# TeensyLED_15042100.net
KiCad netlist of a schematic drawn in EAGLE
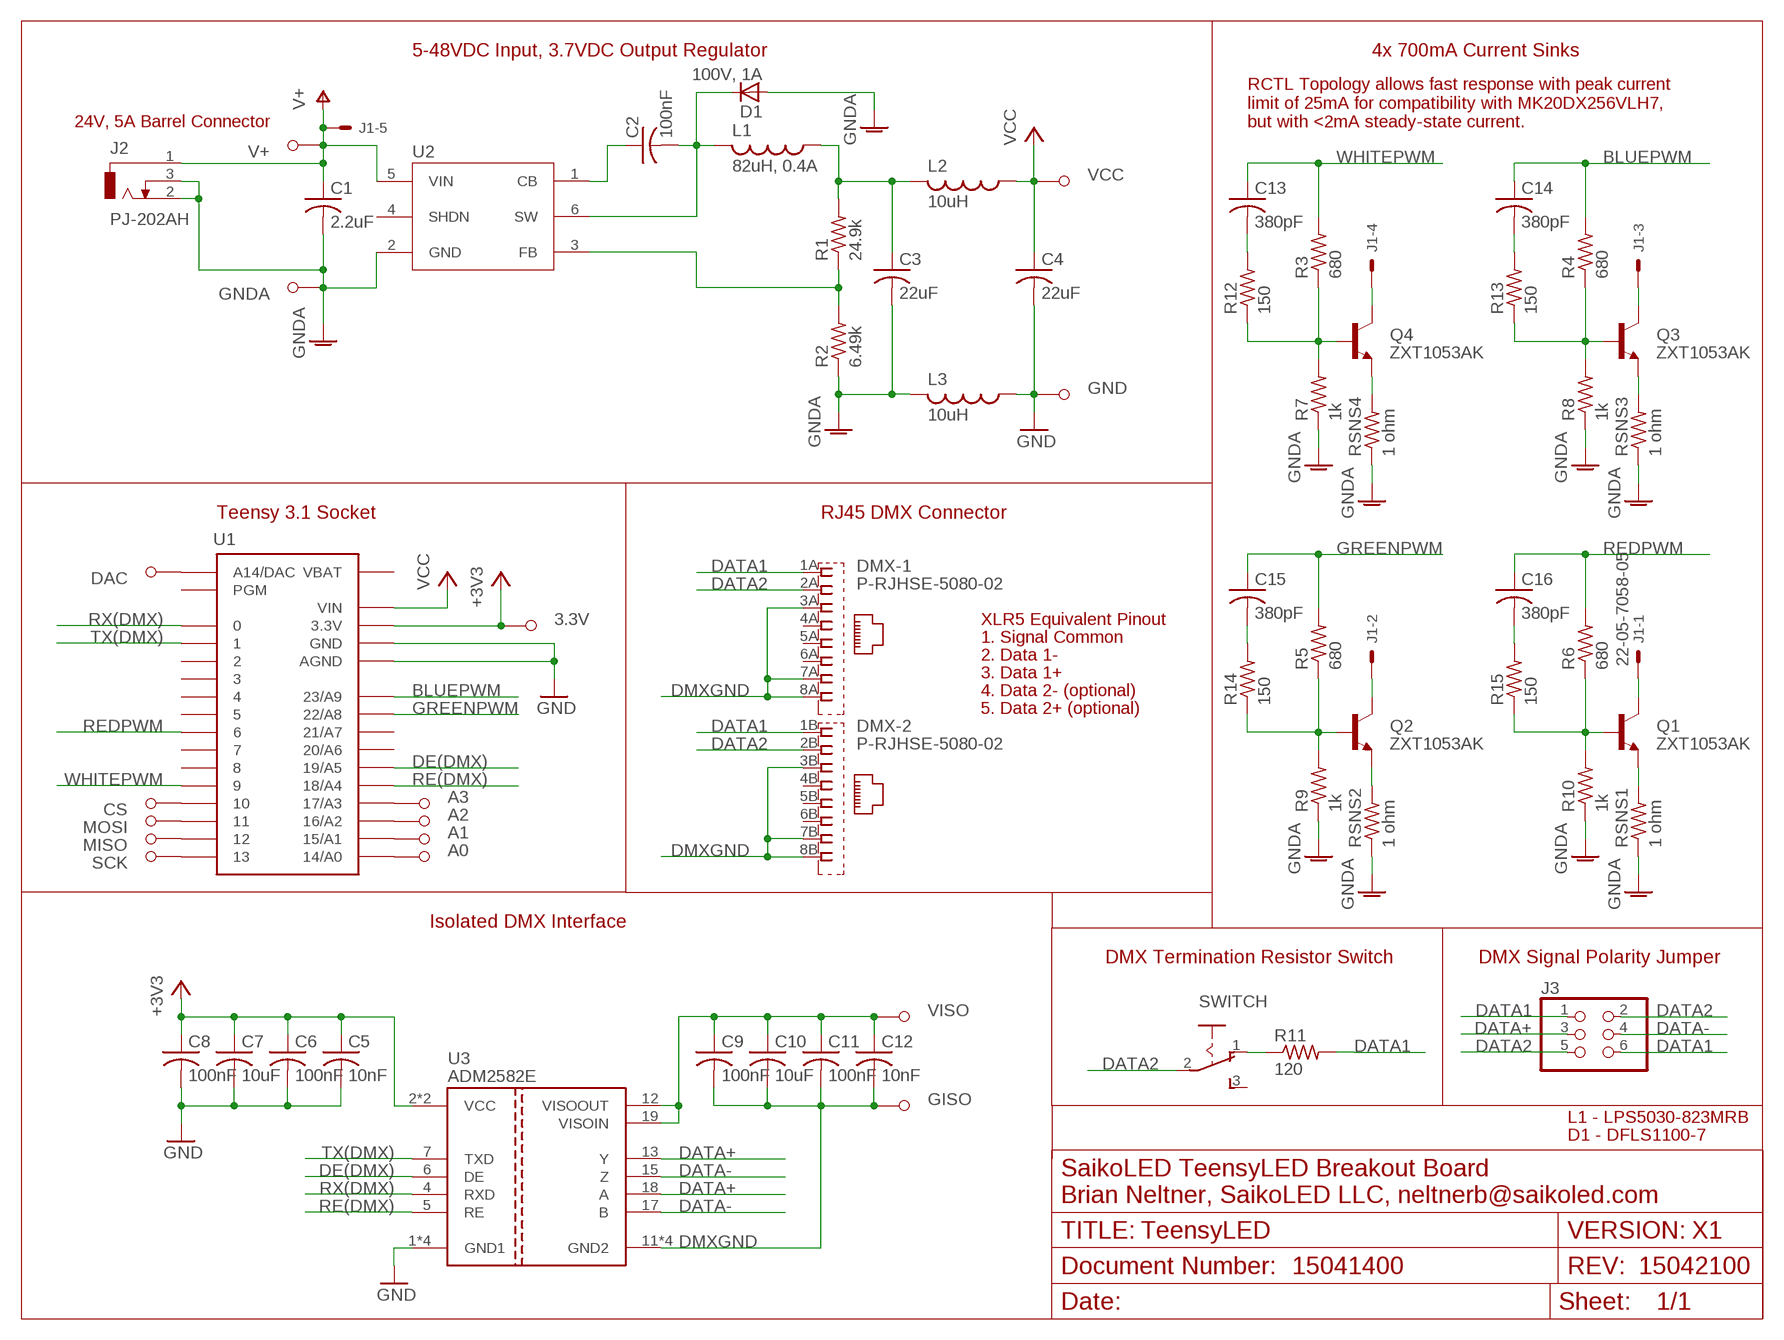
[diagram p0: schematic, sheet 1]

(export (version "E")
  (design (tool "Eeschema 10.0.6"))
  (components
    (comp (ref "3.3V")
      (value "TESTPOINT5019")
      (footprint "eagle-import:5019")
      (libsource (lib "eagle-import") (part "TESTPOINT5019"))
    )
    (comp (ref "A0")
      (value "TESTPOINT5019")
      (footprint "eagle-import:5019")
      (libsource (lib "eagle-import") (part "TESTPOINT5019"))
    )
    (comp (ref "A1")
      (value "TESTPOINT5019")
      (footprint "eagle-import:5019")
      (libsource (lib "eagle-import") (part "TESTPOINT5019"))
    )
    (comp (ref "A2")
      (value "TESTPOINT5019")
      (footprint "eagle-import:5019")
      (libsource (lib "eagle-import") (part "TESTPOINT5019"))
    )
    (comp (ref "A3")
      (value "TESTPOINT5019")
      (footprint "eagle-import:5019")
      (libsource (lib "eagle-import") (part "TESTPOINT5019"))
    )
    (comp (ref "C1")
      (value "2.2uF")
      (footprint "eagle-import:C1210K")
      (libsource (lib "eagle-import") (part "C-USC1210K"))
    )
    (comp (ref "C2")
      (value "100nF")
      (footprint "eagle-import:C0805K")
      (libsource (lib "eagle-import") (part "C-USC0805K"))
    )
    (comp (ref "C3")
      (value "22uF")
      (footprint "eagle-import:C0805K")
      (fields (field (name "MF") "Multicomp Passives") (field (name "MPN") "MCLV4R7M1HB-0513-RH"))
      (libsource (lib "eagle-import") (part "C-USC0805K"))
    )
    (comp (ref "C4")
      (value "22uF")
      (footprint "eagle-import:C0805K")
      (libsource (lib "eagle-import") (part "C-USC0805K"))
    )
    (comp (ref "C5")
      (value "10nF")
      (footprint "eagle-import:C0402PRO")
      (libsource (lib "eagle-import") (part "C-USC0402PRO"))
    )
    (comp (ref "C6")
      (value "100nF")
      (footprint "eagle-import:C0402PRO")
      (libsource (lib "eagle-import") (part "C-USC0402PRO"))
    )
    (comp (ref "C7")
      (value "10uF")
      (footprint "eagle-import:C0402PRO")
      (libsource (lib "eagle-import") (part "C-USC0402PRO"))
    )
    (comp (ref "C8")
      (value "100nF")
      (footprint "eagle-import:C0402PRO")
      (libsource (lib "eagle-import") (part "C-USC0402PRO"))
    )
    (comp (ref "C9")
      (value "100nF")
      (footprint "eagle-import:C0402PRO")
      (libsource (lib "eagle-import") (part "C-USC0402PRO"))
    )
    (comp (ref "C10")
      (value "10uF")
      (footprint "eagle-import:C0402PRO")
      (libsource (lib "eagle-import") (part "C-USC0402PRO"))
    )
    (comp (ref "C11")
      (value "100nF")
      (footprint "eagle-import:C0402PRO")
      (libsource (lib "eagle-import") (part "C-USC0402PRO"))
    )
    (comp (ref "C12")
      (value "10nF")
      (footprint "eagle-import:C0402PRO")
      (libsource (lib "eagle-import") (part "C-USC0402PRO"))
    )
    (comp (ref "C13")
      (value "380pF")
      (footprint "eagle-import:C0402PRO")
      (libsource (lib "eagle-import") (part "C-USC0402PRO"))
    )
    (comp (ref "C14")
      (value "380pF")
      (footprint "eagle-import:C0402PRO")
      (libsource (lib "eagle-import") (part "C-USC0402PRO"))
    )
    (comp (ref "C15")
      (value "380pF")
      (footprint "eagle-import:C0402PRO")
      (libsource (lib "eagle-import") (part "C-USC0402PRO"))
    )
    (comp (ref "C16")
      (value "380pF")
      (footprint "eagle-import:C0402PRO")
      (libsource (lib "eagle-import") (part "C-USC0402PRO"))
    )
    (comp (ref "CS")
      (value "TESTPOINT5019")
      (footprint "eagle-import:5019")
      (libsource (lib "eagle-import") (part "TESTPOINT5019"))
    )
    (comp (ref "D1")
      (value "100V, 1A")
      (footprint "eagle-import:DFLS1100")
      (libsource (lib "eagle-import") (part "DFLS1100"))
    )
    (comp (ref "DAC")
      (value "TESTPOINT5019")
      (footprint "eagle-import:5019")
      (libsource (lib "eagle-import") (part "TESTPOINT5019"))
    )
    (comp (ref "DMX")
      (value "P-RJHSE-5080-02")
      (footprint "eagle-import:P-RJHSE-5080-02")
      (libsource (lib "eagle-import") (part "P-RJHSE-5080-02"))
    )
    (comp (ref "FRAME1")
      (value "LETTER_L")
      (footprint "eagle-import:PCBINFO")
      (libsource (lib "eagle-import") (part "LETTER_L"))
    )
    (comp (ref "GISO")
      (value "TESTPOINT5019")
      (footprint "eagle-import:5019")
      (libsource (lib "eagle-import") (part "TESTPOINT5019"))
    )
    (comp (ref "GND")
      (value "TESTPOINT5019")
      (footprint "eagle-import:5019")
      (libsource (lib "eagle-import") (part "TESTPOINT5019"))
    )
    (comp (ref "GNDA")
      (value "TESTPOINT5019")
      (footprint "eagle-import:5019")
      (libsource (lib "eagle-import") (part "TESTPOINT5019"))
    )
    (comp (ref "J1")
      (value "22-05-7058-05")
      (footprint "eagle-import:7395-05")
      (libsource (lib "eagle-import") (part "22-?-0505-7058"))
    )
    (comp (ref "J2")
      (value "PJ-202AH")
      (footprint "eagle-import:PJ-202AH")
      (libsource (lib "eagle-import") (part "PJ-202AH"))
    )
    (comp (ref "J3")
      (value "PINHD-2X3")
      (footprint "eagle-import:2X03")
      (libsource (lib "eagle-import") (part "PINHD-2X3"))
    )
    (comp (ref "L1")
      (value "82uH, 0.4A")
      (footprint "eagle-import:LPS5030")
      (libsource (lib "eagle-import") (part "L-US"))
    )
    (comp (ref "L2")
      (value "10uH")
      (footprint "eagle-import:L2012C")
      (libsource (lib "eagle-import") (part "rcl_L-USL2012C"))
    )
    (comp (ref "L3")
      (value "10uH")
      (footprint "eagle-import:L2012C")
      (libsource (lib "eagle-import") (part "rcl_L-USL2012C"))
    )
    (comp (ref "MISO")
      (value "TESTPOINT5019")
      (footprint "eagle-import:5019")
      (libsource (lib "eagle-import") (part "TESTPOINT5019"))
    )
    (comp (ref "MOSI")
      (value "TESTPOINT5019")
      (footprint "eagle-import:5019")
      (libsource (lib "eagle-import") (part "TESTPOINT5019"))
    )
    (comp (ref "Q1")
      (value "ZXT1053AK")
      (footprint "eagle-import:TO252")
      (libsource (lib "eagle-import") (part "ZXT1053AK"))
    )
    (comp (ref "Q2")
      (value "ZXT1053AK")
      (footprint "eagle-import:TO252")
      (libsource (lib "eagle-import") (part "ZXT1053AK"))
    )
    (comp (ref "Q3")
      (value "ZXT1053AK")
      (footprint "eagle-import:TO252")
      (libsource (lib "eagle-import") (part "ZXT1053AK"))
    )
    (comp (ref "Q4")
      (value "ZXT1053AK")
      (footprint "eagle-import:TO252")
      (libsource (lib "eagle-import") (part "ZXT1053AK"))
    )
    (comp (ref "R1")
      (value "24.9k")
      (footprint "eagle-import:R0402PRO")
      (fields (field (name "MPN") "BLU0402-9762-BT25W"))
      (libsource (lib "eagle-import") (part "R-US_R0402PRO"))
    )
    (comp (ref "R2")
      (value "6.49k")
      (footprint "eagle-import:R0402PRO")
      (fields (field (name "MPN") "ERJ-3EKF4123V"))
      (libsource (lib "eagle-import") (part "R-US_R0402PRO"))
    )
    (comp (ref "R3")
      (value "680")
      (footprint "eagle-import:R0402PRO")
      (libsource (lib "eagle-import") (part "R-US_R0402PRO"))
    )
    (comp (ref "R4")
      (value "680")
      (footprint "eagle-import:R0402PRO")
      (libsource (lib "eagle-import") (part "R-US_R0402PRO"))
    )
    (comp (ref "R5")
      (value "680")
      (footprint "eagle-import:R0402PRO")
      (libsource (lib "eagle-import") (part "R-US_R0402PRO"))
    )
    (comp (ref "R6")
      (value "680")
      (footprint "eagle-import:R0402PRO")
      (libsource (lib "eagle-import") (part "R-US_R0402PRO"))
    )
    (comp (ref "R7")
      (value "1k")
      (footprint "eagle-import:R0402PRO")
      (libsource (lib "eagle-import") (part "R-US_R0402PRO"))
    )
    (comp (ref "R8")
      (value "1k")
      (footprint "eagle-import:R0402PRO")
      (libsource (lib "eagle-import") (part "R-US_R0402PRO"))
    )
    (comp (ref "R9")
      (value "1k")
      (footprint "eagle-import:R0402PRO")
      (libsource (lib "eagle-import") (part "R-US_R0402PRO"))
    )
    (comp (ref "R10")
      (value "1k")
      (footprint "eagle-import:R0402PRO")
      (libsource (lib "eagle-import") (part "R-US_R0402PRO"))
    )
    (comp (ref "R11")
      (value "120")
      (footprint "eagle-import:R0402PRO")
      (libsource (lib "eagle-import") (part "R-US_R0402PRO"))
    )
    (comp (ref "R12")
      (value "150")
      (footprint "eagle-import:R0402PRO")
      (libsource (lib "eagle-import") (part "R-US_R0402PRO"))
    )
    (comp (ref "R13")
      (value "150")
      (footprint "eagle-import:R0402PRO")
      (libsource (lib "eagle-import") (part "R-US_R0402PRO"))
    )
    (comp (ref "R14")
      (value "150")
      (footprint "eagle-import:R0402PRO")
      (libsource (lib "eagle-import") (part "R-US_R0402PRO"))
    )
    (comp (ref "R15")
      (value "150")
      (footprint "eagle-import:R0402PRO")
      (libsource (lib "eagle-import") (part "R-US_R0402PRO"))
    )
    (comp (ref "RSNS1")
      (value "1 ohm")
      (footprint "eagle-import:R1206")
      (libsource (lib "eagle-import") (part "R-US_R1206"))
    )
    (comp (ref "RSNS2")
      (value "1 ohm")
      (footprint "eagle-import:R1206")
      (libsource (lib "eagle-import") (part "R-US_R1206"))
    )
    (comp (ref "RSNS3")
      (value "1 ohm")
      (footprint "eagle-import:R1206")
      (libsource (lib "eagle-import") (part "R-US_R1206"))
    )
    (comp (ref "RSNS4")
      (value "1 ohm")
      (footprint "eagle-import:R1206")
      (libsource (lib "eagle-import") (part "R-US_R1206"))
    )
    (comp (ref "SCK")
      (value "TESTPOINT5019")
      (footprint "eagle-import:5019")
      (libsource (lib "eagle-import") (part "TESTPOINT5019"))
    )
    (comp (ref "SWITCH")
      (value "M251")
      (footprint "eagle-import:SK-12F17-G")
      (libsource (lib "eagle-import") (part "M251"))
    )
    (comp (ref "U1")
      (value "TEENSY_3.0_BASIC")
      (footprint "eagle-import:TEENSY_3.0_BASIC")
      (libsource (lib "eagle-import") (part "TEENSY_3.0_BASIC"))
    )
    (comp (ref "U2")
      (value "LMR16006YDDCT")
      (footprint "eagle-import:DDC0006A")
      (fields
        (field (name "MANUFACTURER") "Texas Instruments")
        (field (name "PARTNUMBER") "LMR16006YDDC")
        (field (name "MF") "FARNELL")
      )
      (libsource (lib "eagle-import") (part "LMR16006YDDCT"))
    )
    (comp (ref "U3")
      (value "ADM2582E")
      (footprint "eagle-import:SO-20DW")
      (libsource (lib "eagle-import") (part "ADM2582E"))
    )
    (comp (ref "V+")
      (value "TESTPOINT5019")
      (footprint "eagle-import:5019")
      (libsource (lib "eagle-import") (part "TESTPOINT5019"))
    )
    (comp (ref "VCC")
      (value "TESTPOINT5019")
      (footprint "eagle-import:5019")
      (libsource (lib "eagle-import") (part "TESTPOINT5019"))
    )
    (comp (ref "VISO")
      (value "TESTPOINT5019")
      (footprint "eagle-import:5019")
      (libsource (lib "eagle-import") (part "TESTPOINT5019"))
    )
  )
  (nets
    (net (code "1") (name "+3V3") (class "Default")
      (node (ref "3.3V") (pin "P$1") (pinfunction "P$1_P$1") (pintype "passive"))
      (node (ref "C5") (pin "1") (pinfunction "1_1") (pintype "passive"))
      (node (ref "C6") (pin "1") (pinfunction "1_1") (pintype "passive"))
      (node (ref "C7") (pin "1") (pinfunction "1_1") (pintype "passive"))
      (node (ref "C8") (pin "1") (pinfunction "1_1") (pintype "passive"))
      (node (ref "U1") (pin "3.3V") (pinfunction "3.3V_3.3V") (pintype "power_in"))
      (node (ref "U1") (pin "3.3V1") (pinfunction "3.3V_3.3V1") (pintype "power_in"))
      (node (ref "U3") (pin "2") (pinfunction "VCC_2") (pintype "bidirectional"))
      (node (ref "U3") (pin "8") (pinfunction "VCC_8") (pintype "bidirectional"))
    )
    (net (code "2") (name "/BLUEPWM") (class "Default")
      (node (ref "C14") (pin "1") (pinfunction "1_1") (pintype "passive"))
      (node (ref "R4") (pin "2") (pinfunction "2_2") (pintype "passive"))
      (node (ref "U1") (pin "23/A9") (pinfunction "23/A9_23/A9") (pintype "bidirectional"))
    )
    (net (code "3") (name "/DATA+") (class "Default")
      (node (ref "J3") (pin "3") (pinfunction "3_3") (pintype "passive"))
      (node (ref "U3") (pin "13") (pinfunction "Y_13") (pintype "bidirectional"))
      (node (ref "U3") (pin "18") (pinfunction "A_18") (pintype "bidirectional"))
    )
    (net (code "4") (name "/DATA-") (class "Default")
      (node (ref "J3") (pin "4") (pinfunction "4_4") (pintype "passive"))
      (node (ref "U3") (pin "15") (pinfunction "Z_15") (pintype "bidirectional"))
      (node (ref "U3") (pin "17") (pinfunction "B_17") (pintype "bidirectional"))
    )
    (net (code "5") (name "/DATA1") (class "Default")
      (node (ref "DMX") (pin "1A") (pinfunction "1_1A") (pintype "passive"))
      (node (ref "DMX") (pin "1B") (pinfunction "1_1B") (pintype "passive"))
      (node (ref "J3") (pin "1") (pinfunction "1_1") (pintype "passive"))
      (node (ref "J3") (pin "6") (pinfunction "6_6") (pintype "passive"))
      (node (ref "R11") (pin "2") (pinfunction "2_2") (pintype "passive"))
    )
    (net (code "6") (name "/DATA2") (class "Default")
      (node (ref "DMX") (pin "2A") (pinfunction "2_2A") (pintype "passive"))
      (node (ref "DMX") (pin "2B") (pinfunction "2_2B") (pintype "passive"))
      (node (ref "J3") (pin "2") (pinfunction "2_2") (pintype "passive"))
      (node (ref "J3") (pin "5") (pinfunction "5_5") (pintype "passive"))
      (node (ref "SWITCH") (pin "2") (pinfunction "P_2") (pintype "passive"))
    )
    (net (code "7") (name "/DE(DMX)") (class "Default")
      (node (ref "U1") (pin "19/A5") (pinfunction "19/A5_19/A5") (pintype "bidirectional"))
      (node (ref "U3") (pin "6") (pinfunction "DE_6") (pintype "bidirectional"))
    )
    (net (code "8") (name "/DMXGND") (class "Default")
      (node (ref "C10") (pin "2") (pinfunction "2_2") (pintype "passive"))
      (node (ref "C11") (pin "2") (pinfunction "2_2") (pintype "passive"))
      (node (ref "C12") (pin "2") (pinfunction "2_2") (pintype "passive"))
      (node (ref "C9") (pin "2") (pinfunction "2_2") (pintype "passive"))
      (node (ref "DMX") (pin "3A") (pinfunction "3_3A") (pintype "passive"))
      (node (ref "DMX") (pin "3B") (pinfunction "3_3B") (pintype "passive"))
      (node (ref "DMX") (pin "7A") (pinfunction "7_7A") (pintype "passive"))
      (node (ref "DMX") (pin "7B") (pinfunction "7_7B") (pintype "passive"))
      (node (ref "DMX") (pin "8A") (pinfunction "8_8A") (pintype "passive"))
      (node (ref "DMX") (pin "8B") (pinfunction "8_8B") (pintype "passive"))
      (node (ref "GISO") (pin "P$1") (pinfunction "P$1_P$1") (pintype "passive"))
      (node (ref "U3") (pin "11") (pinfunction "GND2_11") (pintype "bidirectional"))
      (node (ref "U3") (pin "14") (pinfunction "GND2_14") (pintype "bidirectional"))
      (node (ref "U3") (pin "16") (pinfunction "GND2_16") (pintype "bidirectional"))
      (node (ref "U3") (pin "20") (pinfunction "GND2_20") (pintype "bidirectional"))
    )
    (net (code "9") (name "/GREENPWM") (class "Default")
      (node (ref "C15") (pin "1") (pinfunction "1_1") (pintype "passive"))
      (node (ref "R5") (pin "2") (pinfunction "2_2") (pintype "passive"))
      (node (ref "U1") (pin "22/A8") (pinfunction "22/A8_22/A8") (pintype "bidirectional"))
    )
    (net (code "10") (name "/RE(DMX)") (class "Default")
      (node (ref "U1") (pin "18/A4") (pinfunction "18/A4_18/A4") (pintype "bidirectional"))
      (node (ref "U3") (pin "5") (pinfunction "RE_5") (pintype "bidirectional"))
    )
    (net (code "11") (name "/REDPWM") (class "Default")
      (node (ref "C16") (pin "1") (pinfunction "1_1") (pintype "passive"))
      (node (ref "R6") (pin "2") (pinfunction "2_2") (pintype "passive"))
      (node (ref "U1") (pin "6") (pinfunction "6_6") (pintype "bidirectional"))
    )
    (net (code "12") (name "/RX(DMX)") (class "Default")
      (node (ref "U1") (pin "0") (pinfunction "0_0") (pintype "bidirectional"))
      (node (ref "U3") (pin "4") (pinfunction "RXD_4") (pintype "bidirectional"))
    )
    (net (code "13") (name "/TX(DMX)") (class "Default")
      (node (ref "U1") (pin "1") (pinfunction "1_1") (pintype "bidirectional"))
      (node (ref "U3") (pin "7") (pinfunction "TXD_7") (pintype "bidirectional"))
    )
    (net (code "14") (name "/VBAT") (class "Default")
      (node (ref "U1") (pin "VBAT") (pinfunction "VBAT_VBAT") (pintype "power_in"))
    )
    (net (code "15") (name "/WHITEPWM") (class "Default")
      (node (ref "C13") (pin "1") (pinfunction "1_1") (pintype "passive"))
      (node (ref "R3") (pin "2") (pinfunction "2_2") (pintype "passive"))
      (node (ref "U1") (pin "9") (pinfunction "9_9") (pintype "bidirectional"))
    )
    (net (code "16") (name "GND") (class "Default")
      (node (ref "C4") (pin "2") (pinfunction "2_2") (pintype "passive"))
      (node (ref "C5") (pin "2") (pinfunction "2_2") (pintype "passive"))
      (node (ref "C6") (pin "2") (pinfunction "2_2") (pintype "passive"))
      (node (ref "C7") (pin "2") (pinfunction "2_2") (pintype "passive"))
      (node (ref "C8") (pin "2") (pinfunction "2_2") (pintype "passive"))
      (node (ref "GND") (pin "P$1") (pinfunction "P$1_P$1") (pintype "passive"))
      (node (ref "L3") (pin "1") (pinfunction "1_1") (pintype "passive"))
      (node (ref "U1") (pin "AGND") (pinfunction "AGND_AGND") (pintype "power_in"))
      (node (ref "U1") (pin "GND") (pinfunction "GND_GND") (pintype "power_in"))
      (node (ref "U1") (pin "GND1") (pinfunction "GND_GND1") (pintype "power_in"))
      (node (ref "U3") (pin "1") (pinfunction "GND1_1") (pintype "bidirectional"))
      (node (ref "U3") (pin "10") (pinfunction "GND1_10") (pintype "bidirectional"))
      (node (ref "U3") (pin "3") (pinfunction "GND1_3") (pintype "bidirectional"))
      (node (ref "U3") (pin "9") (pinfunction "GND1_9") (pintype "bidirectional"))
    )
    (net (code "17") (name "GNDA") (class "Default")
      (node (ref "C1") (pin "2") (pinfunction "2_2") (pintype "passive"))
      (node (ref "C3") (pin "2") (pinfunction "2_2") (pintype "passive"))
      (node (ref "D1") (pin "A") (pinfunction "A_A") (pintype "passive"))
      (node (ref "GNDA") (pin "P$1") (pinfunction "P$1_P$1") (pintype "passive"))
      (node (ref "J2") (pin "2") (pinfunction "3_2") (pintype "passive"))
      (node (ref "J2") (pin "3") (pinfunction "2_3") (pintype "passive"))
      (node (ref "L3") (pin "2") (pinfunction "2_2") (pintype "passive"))
      (node (ref "R10") (pin "1") (pinfunction "1_1") (pintype "passive"))
      (node (ref "R2") (pin "1") (pinfunction "1_1") (pintype "passive"))
      (node (ref "R7") (pin "1") (pinfunction "1_1") (pintype "passive"))
      (node (ref "R8") (pin "1") (pinfunction "1_1") (pintype "passive"))
      (node (ref "R9") (pin "1") (pinfunction "1_1") (pintype "passive"))
      (node (ref "RSNS1") (pin "1") (pinfunction "1_1") (pintype "passive"))
      (node (ref "RSNS2") (pin "1") (pinfunction "1_1") (pintype "passive"))
      (node (ref "RSNS3") (pin "1") (pinfunction "1_1") (pintype "passive"))
      (node (ref "RSNS4") (pin "1") (pinfunction "1_1") (pintype "passive"))
      (node (ref "U2") (pin "2") (pinfunction "GND_2") (pintype "power_in"))
    )
    (net (code "18") (name "Net-(A0-PadP$1)") (class "Default")
      (node (ref "A0") (pin "P$1") (pinfunction "P$1_P$1") (pintype "passive"))
      (node (ref "U1") (pin "14/A0") (pinfunction "14/A0_14/A0") (pintype "bidirectional"))
    )
    (net (code "19") (name "Net-(A1-PadP$1)") (class "Default")
      (node (ref "A1") (pin "P$1") (pinfunction "P$1_P$1") (pintype "passive"))
      (node (ref "U1") (pin "15/A1") (pinfunction "15/A1_15/A1") (pintype "bidirectional"))
    )
    (net (code "20") (name "Net-(A2-PadP$1)") (class "Default")
      (node (ref "A2") (pin "P$1") (pinfunction "P$1_P$1") (pintype "passive"))
      (node (ref "U1") (pin "16/A2") (pinfunction "16/A2_16/A2") (pintype "bidirectional"))
    )
    (net (code "21") (name "Net-(A3-PadP$1)") (class "Default")
      (node (ref "A3") (pin "P$1") (pinfunction "P$1_P$1") (pintype "passive"))
      (node (ref "U1") (pin "17/A3") (pinfunction "17/A3_17/A3") (pintype "bidirectional"))
    )
    (net (code "22") (name "Net-(C13-Pad2)") (class "Default")
      (node (ref "C13") (pin "2") (pinfunction "2_2") (pintype "passive"))
      (node (ref "R12") (pin "2") (pinfunction "2_2") (pintype "passive"))
    )
    (net (code "23") (name "Net-(C14-Pad2)") (class "Default")
      (node (ref "C14") (pin "2") (pinfunction "2_2") (pintype "passive"))
      (node (ref "R13") (pin "2") (pinfunction "2_2") (pintype "passive"))
    )
    (net (code "24") (name "Net-(C15-Pad2)") (class "Default")
      (node (ref "C15") (pin "2") (pinfunction "2_2") (pintype "passive"))
      (node (ref "R14") (pin "2") (pinfunction "2_2") (pintype "passive"))
    )
    (net (code "25") (name "Net-(C16-Pad2)") (class "Default")
      (node (ref "C16") (pin "2") (pinfunction "2_2") (pintype "passive"))
      (node (ref "R15") (pin "2") (pinfunction "2_2") (pintype "passive"))
    )
    (net (code "26") (name "Net-(CS-PadP$1)") (class "Default")
      (node (ref "CS") (pin "P$1") (pinfunction "P$1_P$1") (pintype "passive"))
      (node (ref "U1") (pin "10") (pinfunction "10_10") (pintype "bidirectional"))
    )
    (net (code "27") (name "Net-(J1A-S)") (class "Default")
      (node (ref "J1") (pin "1") (pinfunction "S_1") (pintype "passive"))
      (node (ref "Q1") (pin "C") (pinfunction "C_C") (pintype "passive"))
    )
    (net (code "28") (name "Net-(J1B-S)") (class "Default")
      (node (ref "J1") (pin "2") (pinfunction "S_2") (pintype "passive"))
      (node (ref "Q2") (pin "C") (pinfunction "C_C") (pintype "passive"))
    )
    (net (code "29") (name "Net-(J1C-S)") (class "Default")
      (node (ref "J1") (pin "3") (pinfunction "S_3") (pintype "passive"))
      (node (ref "Q3") (pin "C") (pinfunction "C_C") (pintype "passive"))
    )
    (net (code "30") (name "Net-(J1D-S)") (class "Default")
      (node (ref "J1") (pin "4") (pinfunction "S_4") (pintype "passive"))
      (node (ref "Q4") (pin "C") (pinfunction "C_C") (pintype "passive"))
    )
    (net (code "31") (name "Net-(L1-1)") (class "Default")
      (node (ref "C3") (pin "1") (pinfunction "1_1") (pintype "passive"))
      (node (ref "L1") (pin "P$1") (pinfunction "1_P$1") (pintype "passive"))
      (node (ref "L2") (pin "2") (pinfunction "2_2") (pintype "passive"))
      (node (ref "R1") (pin "2") (pinfunction "2_2") (pintype "passive"))
    )
    (net (code "32") (name "Net-(L1-2)") (class "Default")
      (node (ref "C2") (pin "2") (pinfunction "2_2") (pintype "passive"))
      (node (ref "D1") (pin "C") (pinfunction "C_C") (pintype "passive"))
      (node (ref "L1") (pin "P$2") (pinfunction "2_P$2") (pintype "passive"))
      (node (ref "U2") (pin "6") (pinfunction "SW_6") (pintype "power_in"))
    )
    (net (code "33") (name "Net-(MISO-PadP$1)") (class "Default")
      (node (ref "MISO") (pin "P$1") (pinfunction "P$1_P$1") (pintype "passive"))
      (node (ref "U1") (pin "12") (pinfunction "12_12") (pintype "bidirectional"))
    )
    (net (code "34") (name "Net-(MOSI-PadP$1)") (class "Default")
      (node (ref "MOSI") (pin "P$1") (pinfunction "P$1_P$1") (pintype "passive"))
      (node (ref "U1") (pin "11") (pinfunction "11_11") (pintype "bidirectional"))
    )
    (net (code "35") (name "Net-(Q1-PadB)") (class "Default")
      (node (ref "Q1") (pin "B") (pinfunction "B_B") (pintype "passive"))
      (node (ref "R10") (pin "2") (pinfunction "2_2") (pintype "passive"))
      (node (ref "R15") (pin "1") (pinfunction "1_1") (pintype "passive"))
      (node (ref "R6") (pin "1") (pinfunction "1_1") (pintype "passive"))
    )
    (net (code "36") (name "Net-(Q1-PadE)") (class "Default")
      (node (ref "Q1") (pin "E") (pinfunction "E_E") (pintype "passive"))
      (node (ref "RSNS1") (pin "2") (pinfunction "2_2") (pintype "passive"))
    )
    (net (code "37") (name "Net-(Q2-PadB)") (class "Default")
      (node (ref "Q2") (pin "B") (pinfunction "B_B") (pintype "passive"))
      (node (ref "R14") (pin "1") (pinfunction "1_1") (pintype "passive"))
      (node (ref "R5") (pin "1") (pinfunction "1_1") (pintype "passive"))
      (node (ref "R9") (pin "2") (pinfunction "2_2") (pintype "passive"))
    )
    (net (code "38") (name "Net-(Q2-PadE)") (class "Default")
      (node (ref "Q2") (pin "E") (pinfunction "E_E") (pintype "passive"))
      (node (ref "RSNS2") (pin "2") (pinfunction "2_2") (pintype "passive"))
    )
    (net (code "39") (name "Net-(Q3-PadB)") (class "Default")
      (node (ref "Q3") (pin "B") (pinfunction "B_B") (pintype "passive"))
      (node (ref "R13") (pin "1") (pinfunction "1_1") (pintype "passive"))
      (node (ref "R4") (pin "1") (pinfunction "1_1") (pintype "passive"))
      (node (ref "R8") (pin "2") (pinfunction "2_2") (pintype "passive"))
    )
    (net (code "40") (name "Net-(Q3-PadE)") (class "Default")
      (node (ref "Q3") (pin "E") (pinfunction "E_E") (pintype "passive"))
      (node (ref "RSNS3") (pin "2") (pinfunction "2_2") (pintype "passive"))
    )
    (net (code "41") (name "Net-(Q4-PadB)") (class "Default")
      (node (ref "Q4") (pin "B") (pinfunction "B_B") (pintype "passive"))
      (node (ref "R12") (pin "1") (pinfunction "1_1") (pintype "passive"))
      (node (ref "R3") (pin "1") (pinfunction "1_1") (pintype "passive"))
      (node (ref "R7") (pin "2") (pinfunction "2_2") (pintype "passive"))
    )
    (net (code "42") (name "Net-(Q4-PadE)") (class "Default")
      (node (ref "Q4") (pin "E") (pinfunction "E_E") (pintype "passive"))
      (node (ref "RSNS4") (pin "2") (pinfunction "2_2") (pintype "passive"))
    )
    (net (code "43") (name "Net-(SCK-PadP$1)") (class "Default")
      (node (ref "SCK") (pin "P$1") (pinfunction "P$1_P$1") (pintype "passive"))
      (node (ref "U1") (pin "13") (pinfunction "13_13") (pintype "bidirectional"))
    )
    (net (code "44") (name "Net-(SWITCH-O)") (class "Default")
      (node (ref "R11") (pin "1") (pinfunction "1_1") (pintype "passive"))
      (node (ref "SWITCH") (pin "1") (pinfunction "O_1") (pintype "passive"))
    )
    (net (code "45") (name "Net-(U1-A14{slash}DAC)") (class "Default")
      (node (ref "DAC") (pin "P$1") (pinfunction "P$1_P$1") (pintype "passive"))
      (node (ref "U1") (pin "RESET") (pinfunction "A14/DAC_RESET") (pintype "bidirectional"))
    )
    (net (code "46") (name "Net-(U2-CB)") (class "Default")
      (node (ref "C2") (pin "1") (pinfunction "1_1") (pintype "passive"))
      (node (ref "U2") (pin "1") (pinfunction "CB_1") (pintype "output"))
    )
    (net (code "47") (name "Net-(U2-FB)") (class "Default")
      (node (ref "R1") (pin "1") (pinfunction "1_1") (pintype "passive"))
      (node (ref "R2") (pin "2") (pinfunction "2_2") (pintype "passive"))
      (node (ref "U2") (pin "3") (pinfunction "FB_3") (pintype "input"))
    )
    (net (code "48") (name "Net-(U3-VISOIN)") (class "Default")
      (node (ref "C10") (pin "1") (pinfunction "1_1") (pintype "passive"))
      (node (ref "C11") (pin "1") (pinfunction "1_1") (pintype "passive"))
      (node (ref "C12") (pin "1") (pinfunction "1_1") (pintype "passive"))
      (node (ref "C9") (pin "1") (pinfunction "1_1") (pintype "passive"))
      (node (ref "U3") (pin "12") (pinfunction "VISOOUT_12") (pintype "bidirectional"))
      (node (ref "U3") (pin "19") (pinfunction "VISOIN_19") (pintype "bidirectional"))
      (node (ref "VISO") (pin "P$1") (pinfunction "P$1_P$1") (pintype "passive"))
    )
    (net (code "49") (name "V+") (class "Default")
      (node (ref "C1") (pin "1") (pinfunction "1_1") (pintype "passive"))
      (node (ref "J1") (pin "5") (pinfunction "S_5") (pintype "passive"))
      (node (ref "J2") (pin "1") (pinfunction "1_1") (pintype "passive"))
      (node (ref "U2") (pin "5") (pinfunction "VIN_5") (pintype "power_in"))
      (node (ref "V+") (pin "P$1") (pinfunction "P$1_P$1") (pintype "passive"))
    )
    (net (code "50") (name "VCC") (class "Default")
      (node (ref "C4") (pin "1") (pinfunction "1_1") (pintype "passive"))
      (node (ref "L2") (pin "1") (pinfunction "1_1") (pintype "passive"))
      (node (ref "U1") (pin "VIN") (pinfunction "VIN_VIN") (pintype "power_in"))
      (node (ref "VCC") (pin "P$1") (pinfunction "P$1_P$1") (pintype "passive"))
    )
    (net (code "51") (name "unconnected-(DMXA-4-Pad4A)") (class "Default")
      (node (ref "DMX") (pin "4A") (pinfunction "4_4A") (pintype "passive"))
    )
    (net (code "52") (name "unconnected-(DMXA-5-Pad5A)") (class "Default")
      (node (ref "DMX") (pin "5A") (pinfunction "5_5A") (pintype "passive"))
    )
    (net (code "53") (name "unconnected-(DMXA-6-Pad6A)") (class "Default")
      (node (ref "DMX") (pin "6A") (pinfunction "6_6A") (pintype "passive"))
    )
    (net (code "54") (name "unconnected-(DMXB-4-Pad4B)") (class "Default")
      (node (ref "DMX") (pin "4B") (pinfunction "4_4B") (pintype "passive"))
    )
    (net (code "55") (name "unconnected-(DMXB-5-Pad5B)") (class "Default")
      (node (ref "DMX") (pin "5B") (pinfunction "5_5B") (pintype "passive"))
    )
    (net (code "56") (name "unconnected-(DMXB-6-Pad6B)") (class "Default")
      (node (ref "DMX") (pin "6B") (pinfunction "6_6B") (pintype "passive"))
    )
    (net (code "57") (name "unconnected-(SWITCH-S-Pad3)") (class "Default")
      (node (ref "SWITCH") (pin "3") (pinfunction "S_3") (pintype "passive"))
    )
    (net (code "58") (name "unconnected-(U1-Pad2)") (class "Default")
      (node (ref "U1") (pin "2") (pinfunction "2_2") (pintype "bidirectional"))
    )
    (net (code "59") (name "unconnected-(U1-Pad3)") (class "Default")
      (node (ref "U1") (pin "3") (pinfunction "3_3") (pintype "bidirectional"))
    )
    (net (code "60") (name "unconnected-(U1-Pad4)") (class "Default")
      (node (ref "U1") (pin "4") (pinfunction "4_4") (pintype "bidirectional"))
    )
    (net (code "61") (name "unconnected-(U1-Pad5)") (class "Default")
      (node (ref "U1") (pin "5") (pinfunction "5_5") (pintype "bidirectional"))
    )
    (net (code "62") (name "unconnected-(U1-Pad7)") (class "Default")
      (node (ref "U1") (pin "7") (pinfunction "7_7") (pintype "bidirectional"))
    )
    (net (code "63") (name "unconnected-(U1-Pad8)") (class "Default")
      (node (ref "U1") (pin "8") (pinfunction "8_8") (pintype "bidirectional"))
    )
    (net (code "64") (name "unconnected-(U1-Pad20{slash}A6)") (class "Default")
      (node (ref "U1") (pin "20/A6") (pinfunction "20/A6_20/A6") (pintype "bidirectional"))
    )
    (net (code "65") (name "unconnected-(U1-Pad21{slash}A7)") (class "Default")
      (node (ref "U1") (pin "21/A7") (pinfunction "21/A7_21/A7") (pintype "bidirectional"))
    )
    (net (code "66") (name "unconnected-(U1-PadPGM)") (class "Default")
      (node (ref "U1") (pin "PGM") (pinfunction "PGM_PGM") (pintype "bidirectional"))
    )
    (net (code "67") (name "unconnected-(U2-SHDN-Pad4)") (class "Default")
      (node (ref "U2") (pin "4") (pinfunction "SHDN_4") (pintype "input"))
    )
  )
)
